# thermostat-v100.net
KiCad netlist of a schematic drawn in EAGLE
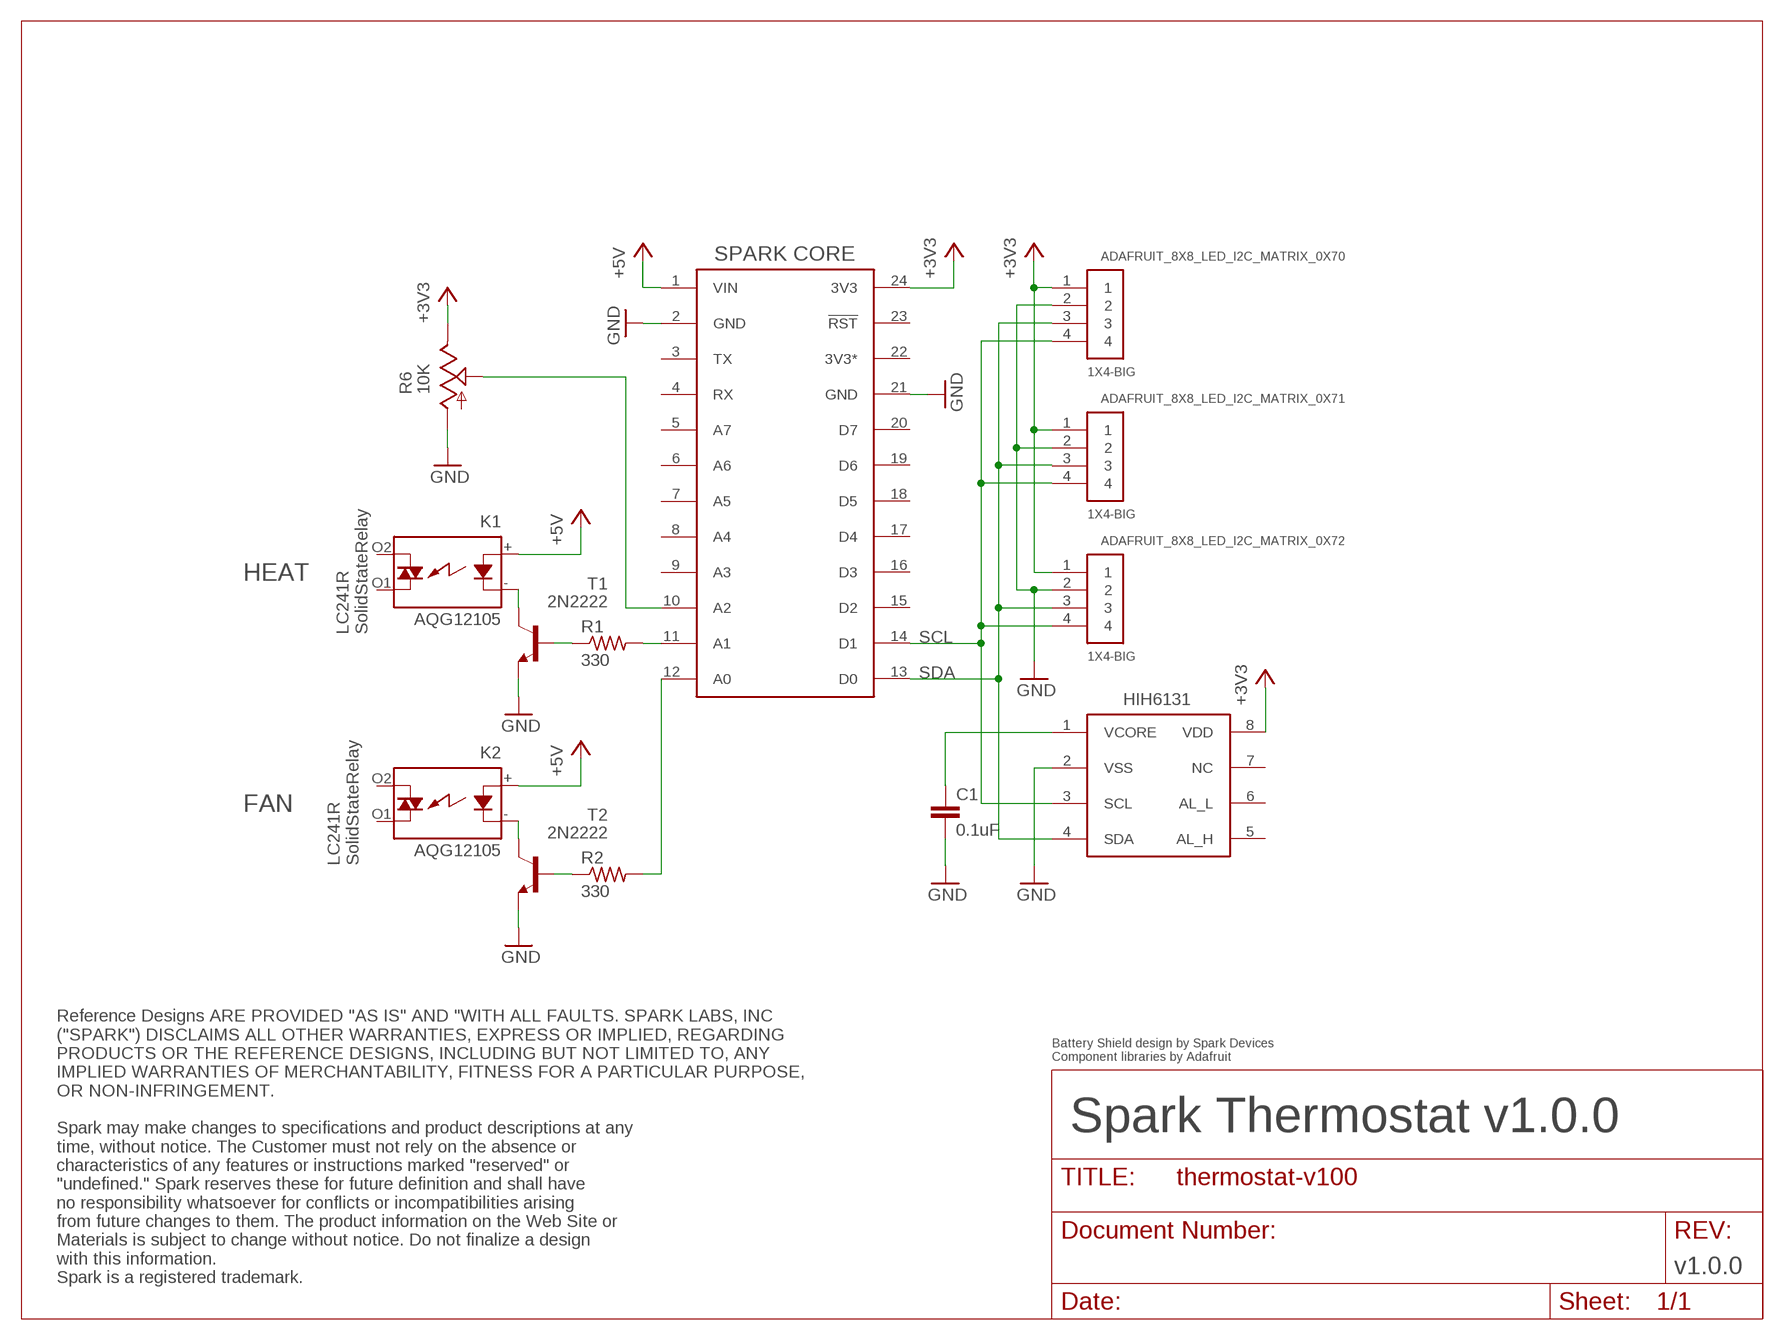
[diagram p0: schematic, sheet 1]

(export (version "E")
  (design (tool "Eeschema 10.0.6"))
  (components
    (comp (ref "ADAFRUIT_8X8_LED_I2C_MATRIX_0X70")
      (value "1X4-BIG")
      (footprint "eagle-import:1X04-BIG")
      (libsource (lib "eagle-import") (part "1X4-BIG"))
    )
    (comp (ref "ADAFRUIT_8X8_LED_I2C_MATRIX_0X71")
      (value "1X4-BIG")
      (footprint "eagle-import:1X04-BIG")
      (libsource (lib "eagle-import") (part "1X4-BIG"))
    )
    (comp (ref "ADAFRUIT_8X8_LED_I2C_MATRIX_0X72")
      (value "1X4-BIG")
      (footprint "eagle-import:1X04-BIG")
      (libsource (lib "eagle-import") (part "1X4-BIG"))
    )
    (comp (ref "C1")
      (value "0.1uF")
      (footprint "eagle-import:C025-024X044")
      (libsource (lib "eagle-import") (part "C-EU025-024X044"))
    )
    (comp (ref "HIH6131")
      (value "HIH6131")
      (footprint "eagle-import:SOIC8")
      (libsource (lib "eagle-import") (part "HIH6131"))
    )
    (comp (ref "K1")
      (value "AQG12105")
      (footprint "eagle-import:AQG")
      (fields (field (name "MF") "AROMAT/ MATSUSHITA"))
      (libsource (lib "eagle-import") (part "AQG12105"))
    )
    (comp (ref "K2")
      (value "AQG12105")
      (footprint "eagle-import:AQG")
      (fields (field (name "MF") "AROMAT/ MATSUSHITA"))
      (libsource (lib "eagle-import") (part "AQG12105"))
    )
    (comp (ref "R1")
      (value "330")
      (footprint "eagle-import:0207_10")
      (libsource (lib "eagle-import") (part "R-US_0207/10"))
    )
    (comp (ref "R2")
      (value "330")
      (footprint "eagle-import:0207_10")
      (libsource (lib "eagle-import") (part "R-US_0207/10"))
    )
    (comp (ref "R6")
      (value "10K")
      (footprint "eagle-import:CIP20C-6MM")
      (libsource (lib "eagle-import") (part "TRIM_US-CIP20C-6MM"))
    )
    (comp (ref "T1")
      (value "2N2222")
      (footprint "eagle-import:TO92-EBC-OVAL")
      (libsource (lib "eagle-import") (part "2N2222"))
    )
    (comp (ref "T2")
      (value "2N2222")
      (footprint "eagle-import:TO92-EBC-OVAL")
      (libsource (lib "eagle-import") (part "2N2222"))
    )
    (comp (ref "U$1")
      (value "SPARK_CORECORE")
      (footprint "eagle-import:SPARK_CORE")
      (libsource (lib "eagle-import") (part "SPARK_CORECORE"))
    )
  )
  (nets
    (net (code "1") (name "+3V3") (class "Default")
      (node (ref "ADAFRUIT_8X8_LED_I2C_MATRIX_0X70") (pin "1") (pinfunction "1_1") (pintype "bidirectional"))
      (node (ref "ADAFRUIT_8X8_LED_I2C_MATRIX_0X71") (pin "1") (pinfunction "1_1") (pintype "bidirectional"))
      (node (ref "ADAFRUIT_8X8_LED_I2C_MATRIX_0X72") (pin "1") (pinfunction "1_1") (pintype "bidirectional"))
      (node (ref "HIH6131") (pin "8") (pinfunction "VDD_8") (pintype "bidirectional"))
      (node (ref "R6") (pin "E") (pinfunction "E_E") (pintype "passive"))
      (node (ref "U$1") (pin "24") (pinfunction "3V3_24") (pintype "power_in"))
    )
    (net (code "2") (name "+5V") (class "Default")
      (node (ref "K1") (pin "+") (pinfunction "A_+") (pintype "passive"))
      (node (ref "K2") (pin "+") (pinfunction "A_+") (pintype "passive"))
      (node (ref "U$1") (pin "1") (pinfunction "VIN_1") (pintype "power_in"))
    )
    (net (code "3") (name "/3V3*") (class "Default")
      (node (ref "U$1") (pin "22") (pinfunction "3V3*_22") (pintype "power_in"))
    )
    (net (code "4") (name "/SCL") (class "Default")
      (node (ref "ADAFRUIT_8X8_LED_I2C_MATRIX_0X70") (pin "4") (pinfunction "4_4") (pintype "bidirectional"))
      (node (ref "ADAFRUIT_8X8_LED_I2C_MATRIX_0X71") (pin "4") (pinfunction "4_4") (pintype "bidirectional"))
      (node (ref "ADAFRUIT_8X8_LED_I2C_MATRIX_0X72") (pin "4") (pinfunction "4_4") (pintype "bidirectional"))
      (node (ref "HIH6131") (pin "3") (pinfunction "SCL_3") (pintype "bidirectional"))
      (node (ref "U$1") (pin "14") (pinfunction "D1_14") (pintype "bidirectional"))
    )
    (net (code "5") (name "/SDA") (class "Default")
      (node (ref "ADAFRUIT_8X8_LED_I2C_MATRIX_0X70") (pin "3") (pinfunction "3_3") (pintype "bidirectional"))
      (node (ref "ADAFRUIT_8X8_LED_I2C_MATRIX_0X71") (pin "3") (pinfunction "3_3") (pintype "bidirectional"))
      (node (ref "ADAFRUIT_8X8_LED_I2C_MATRIX_0X72") (pin "3") (pinfunction "3_3") (pintype "bidirectional"))
      (node (ref "HIH6131") (pin "4") (pinfunction "SDA_4") (pintype "bidirectional"))
      (node (ref "U$1") (pin "13") (pinfunction "D0_13") (pintype "bidirectional"))
    )
    (net (code "6") (name "GND") (class "Default")
      (node (ref "ADAFRUIT_8X8_LED_I2C_MATRIX_0X70") (pin "2") (pinfunction "2_2") (pintype "bidirectional"))
      (node (ref "ADAFRUIT_8X8_LED_I2C_MATRIX_0X71") (pin "2") (pinfunction "2_2") (pintype "bidirectional"))
      (node (ref "ADAFRUIT_8X8_LED_I2C_MATRIX_0X72") (pin "2") (pinfunction "2_2") (pintype "bidirectional"))
      (node (ref "C1") (pin "2") (pinfunction "2_2") (pintype "passive"))
      (node (ref "HIH6131") (pin "2") (pinfunction "VSS_2") (pintype "bidirectional"))
      (node (ref "R6") (pin "A") (pinfunction "A_A") (pintype "passive"))
      (node (ref "T1") (pin "E") (pinfunction "E_E") (pintype "passive"))
      (node (ref "T2") (pin "E") (pinfunction "E_E") (pintype "passive"))
      (node (ref "U$1") (pin "2") (pinfunction "GND_2") (pintype "power_in"))
      (node (ref "U$1") (pin "21") (pinfunction "GND_21") (pintype "power_in"))
    )
    (net (code "7") (name "Net-(HIH6131-VCORE)") (class "Default")
      (node (ref "C1") (pin "1") (pinfunction "1_1") (pintype "passive"))
      (node (ref "HIH6131") (pin "1") (pinfunction "VCORE_1") (pintype "bidirectional"))
    )
    (net (code "8") (name "Net-(K1-K)") (class "Default")
      (node (ref "K1") (pin "-") (pinfunction "K_-") (pintype "passive"))
      (node (ref "T1") (pin "C") (pinfunction "C_C") (pintype "passive"))
    )
    (net (code "9") (name "Net-(K2-K)") (class "Default")
      (node (ref "K2") (pin "-") (pinfunction "K_-") (pintype "passive"))
      (node (ref "T2") (pin "C") (pinfunction "C_C") (pintype "passive"))
    )
    (net (code "10") (name "Net-(R1-Pad1)") (class "Default")
      (node (ref "R1") (pin "1") (pinfunction "1_1") (pintype "passive"))
      (node (ref "T1") (pin "B") (pinfunction "B_B") (pintype "passive"))
    )
    (net (code "11") (name "Net-(R2-Pad1)") (class "Default")
      (node (ref "R2") (pin "1") (pinfunction "1_1") (pintype "passive"))
      (node (ref "T2") (pin "B") (pinfunction "B_B") (pintype "passive"))
    )
    (net (code "12") (name "Net-(U$1-A0)") (class "Default")
      (node (ref "R2") (pin "2") (pinfunction "2_2") (pintype "passive"))
      (node (ref "U$1") (pin "12") (pinfunction "A0_12") (pintype "bidirectional"))
    )
    (net (code "13") (name "Net-(U$1-A1)") (class "Default")
      (node (ref "R1") (pin "2") (pinfunction "2_2") (pintype "passive"))
      (node (ref "U$1") (pin "11") (pinfunction "A1_11") (pintype "bidirectional"))
    )
    (net (code "14") (name "Net-(U$1-A2)") (class "Default")
      (node (ref "R6") (pin "S") (pinfunction "S_S") (pintype "passive"))
      (node (ref "U$1") (pin "10") (pinfunction "A2_10") (pintype "bidirectional"))
    )
    (net (code "15") (name "unconnected-(HIH6131-AL_H-Pad5)") (class "Default")
      (node (ref "HIH6131") (pin "5") (pinfunction "AL_H_5") (pintype "bidirectional"))
    )
    (net (code "16") (name "unconnected-(HIH6131-AL_L-Pad6)") (class "Default")
      (node (ref "HIH6131") (pin "6") (pinfunction "AL_L_6") (pintype "bidirectional"))
    )
    (net (code "17") (name "unconnected-(HIH6131-NC-Pad7)") (class "Default")
      (node (ref "HIH6131") (pin "7") (pinfunction "NC_7") (pintype "bidirectional"))
    )
    (net (code "18") (name "unconnected-(K1-DS1-PadO2)") (class "Default")
      (node (ref "K1") (pin "O2") (pinfunction "DS1_O2") (pintype "passive"))
    )
    (net (code "19") (name "unconnected-(K1-DS2-PadO1)") (class "Default")
      (node (ref "K1") (pin "O1") (pinfunction "DS2_O1") (pintype "passive"))
    )
    (net (code "20") (name "unconnected-(K2-DS1-PadO2)") (class "Default")
      (node (ref "K2") (pin "O2") (pinfunction "DS1_O2") (pintype "passive"))
    )
    (net (code "21") (name "unconnected-(K2-DS2-PadO1)") (class "Default")
      (node (ref "K2") (pin "O1") (pinfunction "DS2_O1") (pintype "passive"))
    )
    (net (code "22") (name "unconnected-(U$1-A3-Pad9)") (class "Default")
      (node (ref "U$1") (pin "9") (pinfunction "A3_9") (pintype "bidirectional"))
    )
    (net (code "23") (name "unconnected-(U$1-A4-Pad8)") (class "Default")
      (node (ref "U$1") (pin "8") (pinfunction "A4_8") (pintype "bidirectional"))
    )
    (net (code "24") (name "unconnected-(U$1-A5-Pad7)") (class "Default")
      (node (ref "U$1") (pin "7") (pinfunction "A5_7") (pintype "bidirectional"))
    )
    (net (code "25") (name "unconnected-(U$1-A6-Pad6)") (class "Default")
      (node (ref "U$1") (pin "6") (pinfunction "A6_6") (pintype "bidirectional"))
    )
    (net (code "26") (name "unconnected-(U$1-A7-Pad5)") (class "Default")
      (node (ref "U$1") (pin "5") (pinfunction "A7_5") (pintype "bidirectional"))
    )
    (net (code "27") (name "unconnected-(U$1-D2-Pad15)") (class "Default")
      (node (ref "U$1") (pin "15") (pinfunction "D2_15") (pintype "bidirectional"))
    )
    (net (code "28") (name "unconnected-(U$1-D3-Pad16)") (class "Default")
      (node (ref "U$1") (pin "16") (pinfunction "D3_16") (pintype "bidirectional"))
    )
    (net (code "29") (name "unconnected-(U$1-D4-Pad17)") (class "Default")
      (node (ref "U$1") (pin "17") (pinfunction "D4_17") (pintype "bidirectional"))
    )
    (net (code "30") (name "unconnected-(U$1-D5-Pad18)") (class "Default")
      (node (ref "U$1") (pin "18") (pinfunction "D5_18") (pintype "bidirectional"))
    )
    (net (code "31") (name "unconnected-(U$1-D6-Pad19)") (class "Default")
      (node (ref "U$1") (pin "19") (pinfunction "D6_19") (pintype "bidirectional"))
    )
    (net (code "32") (name "unconnected-(U$1-D7-Pad20)") (class "Default")
      (node (ref "U$1") (pin "20") (pinfunction "D7_20") (pintype "bidirectional"))
    )
    (net (code "33") (name "unconnected-(U$1-RX-Pad4)") (class "Default")
      (node (ref "U$1") (pin "4") (pinfunction "RX_4") (pintype "bidirectional"))
    )
    (net (code "34") (name "unconnected-(U$1-TX-Pad3)") (class "Default")
      (node (ref "U$1") (pin "3") (pinfunction "TX_3") (pintype "bidirectional"))
    )
    (net (code "35") (name "unconnected-(U$1-~{RST}-Pad23)") (class "Default")
      (node (ref "U$1") (pin "23") (pinfunction "~{RST}_23") (pintype "bidirectional"))
    )
  )
)
